# 06_i2cDisplay.net
KiCad netlist of a schematic drawn in Altium Designer
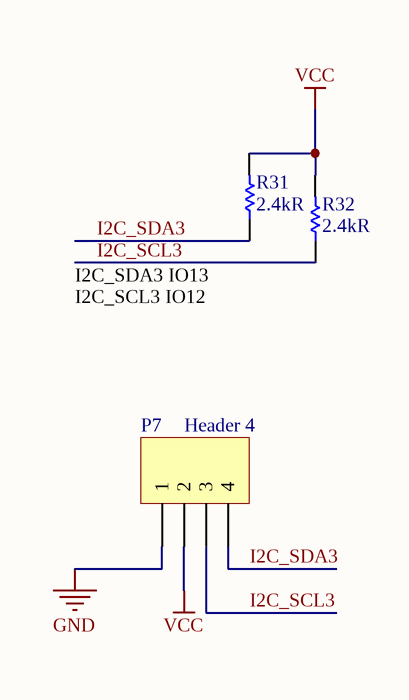
[diagram p0: 06_i2cDisplay.SchDoc]

(export (version "E")
  (design (tool "Eeschema 10.0.6"))
  (components
    (comp (ref "P7")
      (value "Header 4")
      (footprint "HDR1X4")
      (description "Header, 4-Pin")
      (fields (field (name "PUBLISHER") "Altium Limited"))
      (libsource (lib "Miscellaneous Connectors") (part "Header 4"))
    )
    (comp (ref "R31")
      (value "2.4kR")
      (footprint "RESC1608X50X30ML20T20")
      (fields (field (name "PART NUMBER") "RR0816P-242-D") (field (name "MANUFACTURER") "Susumu"))
      (libsource (lib "Altium Content Vault") (part "RES"))
    )
    (comp (ref "R32")
      (value "2.4kR")
      (footprint "RESC1608X50X30ML20T20")
      (fields (field (name "PART NUMBER") "RR0816P-242-D") (field (name "MANUFACTURER") "Susumu"))
      (libsource (lib "Altium Content Vault") (part "RES"))
    )
  )
  (nets
    (net (code "1") (name "/I2C_SCL3") (class "Default")
      (node (ref "P7") (pin "3") (pinfunction "3_3") (pintype "passive"))
      (node (ref "R32") (pin "1") (pinfunction "1_1") (pintype "passive"))
    )
    (net (code "2") (name "/I2C_SDA3") (class "Default")
      (node (ref "P7") (pin "4") (pinfunction "4_4") (pintype "passive"))
      (node (ref "R31") (pin "1") (pinfunction "1_1") (pintype "passive"))
    )
    (net (code "3") (name "GND") (class "Default")
      (node (ref "P7") (pin "1") (pinfunction "1_1") (pintype "passive"))
    )
    (net (code "4") (name "VCC") (class "Default")
      (node (ref "P7") (pin "2") (pinfunction "2_2") (pintype "passive"))
      (node (ref "R31") (pin "2") (pinfunction "2_2") (pintype "passive"))
      (node (ref "R32") (pin "2") (pinfunction "2_2") (pintype "passive"))
    )
  )
)
